# decoder.net
KiCad netlist of a schematic drawn in EAGLE
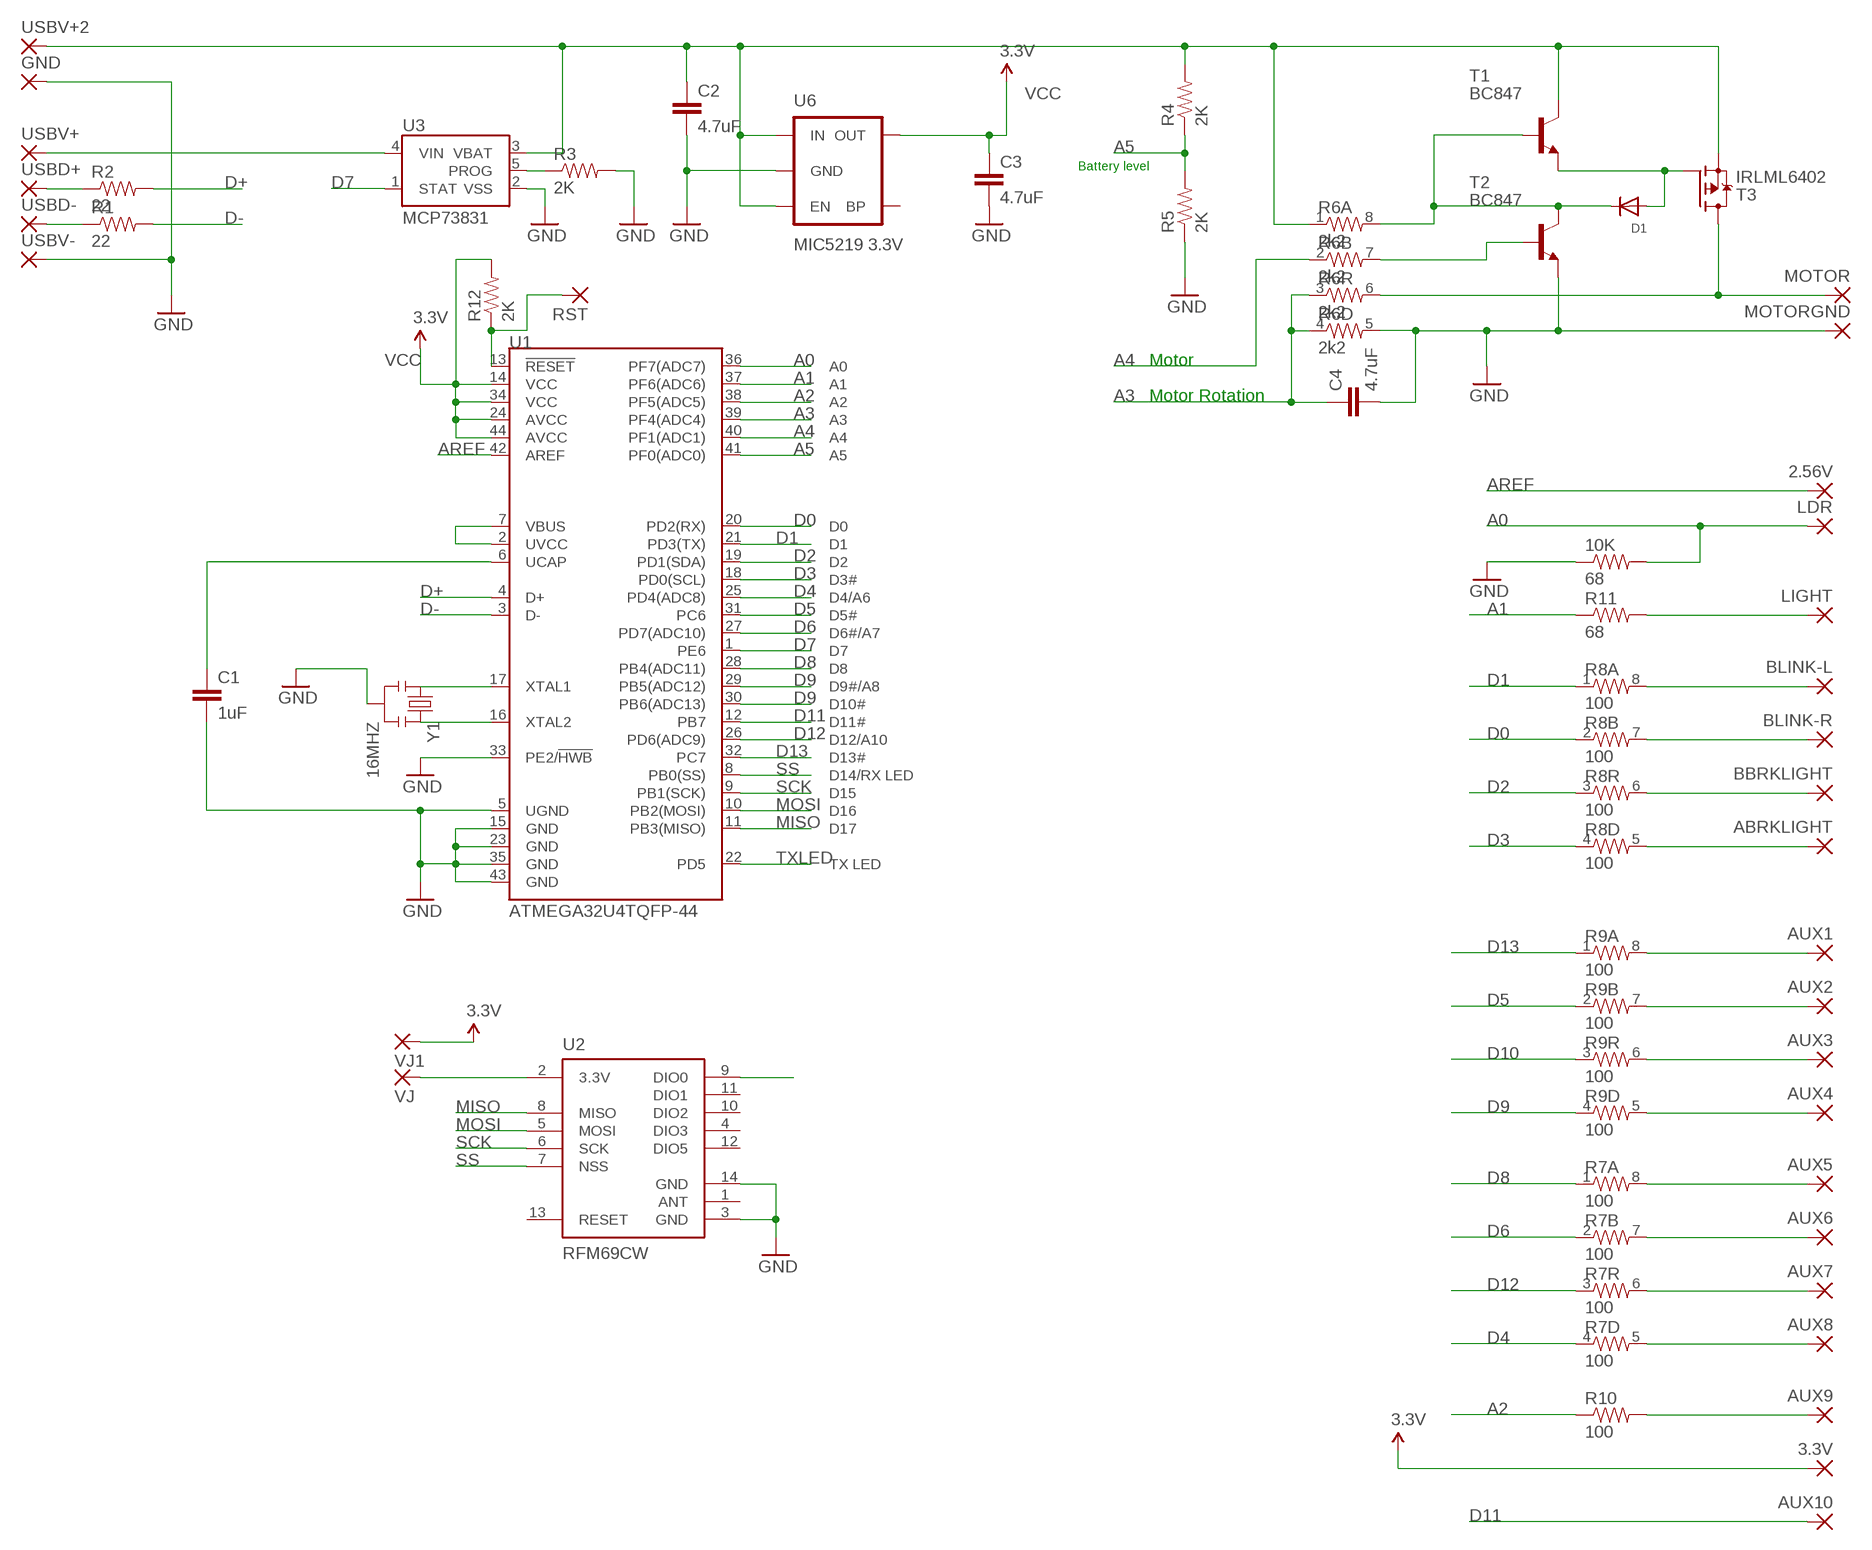
[diagram p0: schematic, sheet 1]

(export (version "E")
  (design (tool "Eeschema 10.0.6"))
  (components
    (comp (ref "2.56V")
      (value "SMD2")
      (footprint "eagle-import:SMD1,27-2,54")
      (libsource (lib "eagle-import") (part "SMD2"))
    )
    (comp (ref "3.3V")
      (value "SMD2")
      (footprint "eagle-import:SMD1,27-2,54")
      (libsource (lib "eagle-import") (part "SMD2"))
    )
    (comp (ref "10K")
      (value "68")
      (footprint "eagle-import:0603-RES")
      (libsource (lib "eagle-import") (part "RESISTOR0603-RES"))
    )
    (comp (ref "ABRKLIGHT")
      (value "SMD2")
      (footprint "eagle-import:SMD1,27-2,54")
      (libsource (lib "eagle-import") (part "SMD2"))
    )
    (comp (ref "AUX1")
      (value "SMD2")
      (footprint "eagle-import:SMD1,27-2,54")
      (libsource (lib "eagle-import") (part "SMD2"))
    )
    (comp (ref "AUX2")
      (value "SMD2")
      (footprint "eagle-import:SMD1,27-2,54")
      (libsource (lib "eagle-import") (part "SMD2"))
    )
    (comp (ref "AUX3")
      (value "SMD2")
      (footprint "eagle-import:SMD1,27-2,54")
      (libsource (lib "eagle-import") (part "SMD2"))
    )
    (comp (ref "AUX4")
      (value "SMD2")
      (footprint "eagle-import:SMD1,27-2,54")
      (libsource (lib "eagle-import") (part "SMD2"))
    )
    (comp (ref "AUX5")
      (value "SMD2")
      (footprint "eagle-import:SMD1,27-2,54")
      (libsource (lib "eagle-import") (part "SMD2"))
    )
    (comp (ref "AUX6")
      (value "SMD2")
      (footprint "eagle-import:SMD1,27-2,54")
      (libsource (lib "eagle-import") (part "SMD2"))
    )
    (comp (ref "AUX7")
      (value "SMD2")
      (footprint "eagle-import:SMD1,27-2,54")
      (libsource (lib "eagle-import") (part "SMD2"))
    )
    (comp (ref "AUX8")
      (value "SMD2")
      (footprint "eagle-import:SMD1,27-2,54")
      (libsource (lib "eagle-import") (part "SMD2"))
    )
    (comp (ref "AUX9")
      (value "SMD2")
      (footprint "eagle-import:SMD1,27-2,54")
      (libsource (lib "eagle-import") (part "SMD2"))
    )
    (comp (ref "AUX10")
      (value "SMD2")
      (footprint "eagle-import:SMD1,27-2,54")
      (libsource (lib "eagle-import") (part "SMD2"))
    )
    (comp (ref "BBRKLIGHT")
      (value "SMD2")
      (footprint "eagle-import:SMD1,27-2,54")
      (libsource (lib "eagle-import") (part "SMD2"))
    )
    (comp (ref "BLINK-L")
      (value "SMD2")
      (footprint "eagle-import:SMD1,27-2,54")
      (libsource (lib "eagle-import") (part "SMD2"))
    )
    (comp (ref "BLINK-R")
      (value "SMD2")
      (footprint "eagle-import:SMD1,27-2,54")
      (libsource (lib "eagle-import") (part "SMD2"))
    )
    (comp (ref "C1")
      (value "1uF")
      (footprint "eagle-import:0805")
      (libsource (lib "eagle-import") (part "CAP0805"))
    )
    (comp (ref "C2")
      (value "4.7uF")
      (footprint "eagle-import:0805")
      (libsource (lib "eagle-import") (part "CAP0805"))
    )
    (comp (ref "C3")
      (value "4.7uF")
      (footprint "eagle-import:0805")
      (libsource (lib "eagle-import") (part "CAP0805"))
    )
    (comp (ref "C4")
      (value "4.7uF")
      (footprint "eagle-import:0805")
      (libsource (lib "eagle-import") (part "CAP0805"))
    )
    (comp (ref "D1")
      (value "DIODESOD-523")
      (footprint "eagle-import:SOD-523")
      (libsource (lib "eagle-import") (part "DIODESOD-523"))
    )
    (comp (ref "GND")
      (value "SMD2")
      (footprint "eagle-import:SMD1,27-2,54")
      (libsource (lib "eagle-import") (part "SMD2"))
    )
    (comp (ref "LDR")
      (value "SMD2")
      (footprint "eagle-import:SMD1,27-2,54")
      (libsource (lib "eagle-import") (part "SMD2"))
    )
    (comp (ref "LIGHT")
      (value "SMD2")
      (footprint "eagle-import:SMD1,27-2,54")
      (libsource (lib "eagle-import") (part "SMD2"))
    )
    (comp (ref "MOTOR")
      (value "SMD2")
      (footprint "eagle-import:SMD1,27-2,54")
      (libsource (lib "eagle-import") (part "SMD2"))
    )
    (comp (ref "MOTORGND")
      (value "SMD2")
      (footprint "eagle-import:SMD1,27-2,54")
      (libsource (lib "eagle-import") (part "SMD2"))
    )
    (comp (ref "R1")
      (value "22")
      (footprint "eagle-import:0603-RES")
      (libsource (lib "eagle-import") (part "RESISTOR0603-RES"))
    )
    (comp (ref "R2")
      (value "22")
      (footprint "eagle-import:0603-RES")
      (libsource (lib "eagle-import") (part "RESISTOR0603-RES"))
    )
    (comp (ref "R3")
      (value "2K")
      (footprint "eagle-import:0603-RES")
      (libsource (lib "eagle-import") (part "RESISTOR0603-RES"))
    )
    (comp (ref "R4")
      (value "2K")
      (footprint "eagle-import:0603-RES")
      (libsource (lib "eagle-import") (part "RESISTOR0603-RES"))
    )
    (comp (ref "R5")
      (value "2K")
      (footprint "eagle-import:0603-RES")
      (libsource (lib "eagle-import") (part "RESISTOR0603-RES"))
    )
    (comp (ref "R6")
      (value "2k2")
      (footprint "eagle-import:0603-ARV")
      (libsource (lib "eagle-import") (part "RESISTOR-ARRAY0603-ARV"))
    )
    (comp (ref "R7")
      (value "100")
      (footprint "eagle-import:0603-ARV")
      (libsource (lib "eagle-import") (part "RESISTOR-ARRAY0603-ARV"))
    )
    (comp (ref "R8")
      (value "100")
      (footprint "eagle-import:0603-ARV")
      (libsource (lib "eagle-import") (part "RESISTOR-ARRAY0603-ARV"))
    )
    (comp (ref "R9")
      (value "100")
      (footprint "eagle-import:0603-ARV")
      (libsource (lib "eagle-import") (part "RESISTOR-ARRAY0603-ARV"))
    )
    (comp (ref "R10")
      (value "100")
      (footprint "eagle-import:0603-RES")
      (libsource (lib "eagle-import") (part "RESISTOR0603-RES"))
    )
    (comp (ref "R11")
      (value "68")
      (footprint "eagle-import:0603-RES")
      (libsource (lib "eagle-import") (part "RESISTOR0603-RES"))
    )
    (comp (ref "R12")
      (value "2K")
      (footprint "eagle-import:0603-RES")
      (libsource (lib "eagle-import") (part "RESISTOR0603-RES"))
    )
    (comp (ref "RST")
      (value "SMD2")
      (footprint "eagle-import:SMD1,27-2,54")
      (libsource (lib "eagle-import") (part "SMD2"))
    )
    (comp (ref "T1")
      (value "BC847")
      (footprint "eagle-import:SOT23")
      (libsource (lib "eagle-import") (part "BC847"))
    )
    (comp (ref "T2")
      (value "BC847")
      (footprint "eagle-import:SOT23")
      (libsource (lib "eagle-import") (part "BC847"))
    )
    (comp (ref "T3")
      (value "IRLML6402")
      (footprint "eagle-import:SOT23")
      (libsource (lib "eagle-import") (part "MOSFET-P-SOT23"))
    )
    (comp (ref "U1")
      (value "ATMEGA32U4TQFP-44")
      (footprint "eagle-import:TQFP44")
      (libsource (lib "eagle-import") (part "ATMEGA32U4TQFP-44"))
    )
    (comp (ref "U2")
      (value "RFM69CW")
      (footprint "eagle-import:RFM69CW-XXXS2")
      (libsource (lib "eagle-import") (part "RFM69CW"))
    )
    (comp (ref "U3")
      (value "MCP73831")
      (footprint "eagle-import:SOT23-5")
      (libsource (lib "eagle-import") (part "MCP73831"))
    )
    (comp (ref "U6")
      (value "MIC5219 3.3V")
      (footprint "eagle-import:SOT23-5")
      (libsource (lib "eagle-import") (part "V_REG_MIC52193.3V"))
    )
    (comp (ref "USBD+")
      (value "SMD2")
      (footprint "eagle-import:SMD1,27-2,54")
      (libsource (lib "eagle-import") (part "SMD2"))
    )
    (comp (ref "USBD-")
      (value "SMD2")
      (footprint "eagle-import:SMD1,27-2,54")
      (libsource (lib "eagle-import") (part "SMD2"))
    )
    (comp (ref "USBV+")
      (value "SMD2")
      (footprint "eagle-import:SMD1,27-2,54")
      (libsource (lib "eagle-import") (part "SMD2"))
    )
    (comp (ref "USBV+2")
      (value "SMD2")
      (footprint "eagle-import:SMD1,27-2,54")
      (libsource (lib "eagle-import") (part "SMD2"))
    )
    (comp (ref "USBV-")
      (value "SMD2")
      (footprint "eagle-import:SMD1,27-2,54")
      (libsource (lib "eagle-import") (part "SMD2"))
    )
    (comp (ref "VJ")
      (value "SMD2")
      (footprint "eagle-import:SMD1,27-2,54")
      (libsource (lib "eagle-import") (part "SMD2"))
    )
    (comp (ref "VJ1")
      (value "SMD2")
      (footprint "eagle-import:SMD1,27-2,54")
      (libsource (lib "eagle-import") (part "SMD2"))
    )
    (comp (ref "Y1")
      (value "16MHZ")
      (footprint "eagle-import:RESONATOR-SMD")
      (libsource (lib "eagle-import") (part "RESONATOR16MHZ"))
    )
  )
  (nets
    (net (code "1") (name "/A0") (class "Default")
      (node (ref "10K") (pin "2") (pinfunction "2_2") (pintype "passive"))
      (node (ref "LDR") (pin "1") (pinfunction "P_1") (pintype "passive"))
      (node (ref "U1") (pin "36") (pinfunction "PF7(ADC7)_36") (pintype "bidirectional"))
    )
    (net (code "2") (name "/A1") (class "Default")
      (node (ref "R11") (pin "1") (pinfunction "1_1") (pintype "passive"))
      (node (ref "U1") (pin "37") (pinfunction "PF6(ADC6)_37") (pintype "bidirectional"))
    )
    (net (code "3") (name "/A2") (class "Default")
      (node (ref "R10") (pin "1") (pinfunction "1_1") (pintype "passive"))
      (node (ref "U1") (pin "38") (pinfunction "PF5(ADC5)_38") (pintype "bidirectional"))
    )
    (net (code "4") (name "/A3") (class "Default")
      (node (ref "C4") (pin "1") (pinfunction "1_1") (pintype "passive"))
      (node (ref "R6") (pin "3") (pinfunction "1_3") (pintype "passive"))
      (node (ref "R6") (pin "4") (pinfunction "1_4") (pintype "passive"))
      (node (ref "U1") (pin "39") (pinfunction "PF4(ADC4)_39") (pintype "bidirectional"))
    )
    (net (code "5") (name "/A4") (class "Default")
      (node (ref "R6") (pin "2") (pinfunction "1_2") (pintype "passive"))
      (node (ref "U1") (pin "40") (pinfunction "PF1(ADC1)_40") (pintype "bidirectional"))
    )
    (net (code "6") (name "/A5") (class "Default")
      (node (ref "R4") (pin "1") (pinfunction "1_1") (pintype "passive"))
      (node (ref "R5") (pin "2") (pinfunction "2_2") (pintype "passive"))
      (node (ref "U1") (pin "41") (pinfunction "PF0(ADC0)_41") (pintype "bidirectional"))
    )
    (net (code "7") (name "/AREF") (class "Default")
      (node (ref "2.56V") (pin "1") (pinfunction "P_1") (pintype "passive"))
      (node (ref "U1") (pin "42") (pinfunction "AREF_42") (pintype "bidirectional"))
    )
    (net (code "8") (name "/D+") (class "Default")
      (node (ref "R2") (pin "2") (pinfunction "2_2") (pintype "passive"))
      (node (ref "U1") (pin "4") (pinfunction "D+_4") (pintype "bidirectional"))
    )
    (net (code "9") (name "/D-") (class "Default")
      (node (ref "R1") (pin "2") (pinfunction "2_2") (pintype "passive"))
      (node (ref "U1") (pin "3") (pinfunction "D-_3") (pintype "bidirectional"))
    )
    (net (code "10") (name "/D0") (class "Default")
      (node (ref "R8") (pin "2") (pinfunction "1_2") (pintype "passive"))
      (node (ref "U1") (pin "20") (pinfunction "PD2(RX)_20") (pintype "bidirectional"))
    )
    (net (code "11") (name "/D1") (class "Default")
      (node (ref "R8") (pin "1") (pinfunction "1_1") (pintype "passive"))
      (node (ref "U1") (pin "21") (pinfunction "PD3(TX)_21") (pintype "bidirectional"))
    )
    (net (code "12") (name "/D2") (class "Default")
      (node (ref "R8") (pin "3") (pinfunction "1_3") (pintype "passive"))
      (node (ref "U1") (pin "19") (pinfunction "PD1(SDA)_19") (pintype "bidirectional"))
      (node (ref "U2") (pin "9") (pinfunction "DIO0_9") (pintype "bidirectional"))
    )
    (net (code "13") (name "/D3") (class "Default")
      (node (ref "R8") (pin "4") (pinfunction "1_4") (pintype "passive"))
      (node (ref "U1") (pin "18") (pinfunction "PD0(SCL)_18") (pintype "bidirectional"))
    )
    (net (code "14") (name "/D4") (class "Default")
      (node (ref "R7") (pin "4") (pinfunction "1_4") (pintype "passive"))
      (node (ref "U1") (pin "25") (pinfunction "PD4(ADC8)_25") (pintype "bidirectional"))
    )
    (net (code "15") (name "/D5") (class "Default")
      (node (ref "R9") (pin "2") (pinfunction "1_2") (pintype "passive"))
      (node (ref "U1") (pin "31") (pinfunction "PC6_31") (pintype "bidirectional"))
    )
    (net (code "16") (name "/D6") (class "Default")
      (node (ref "R7") (pin "2") (pinfunction "1_2") (pintype "passive"))
      (node (ref "U1") (pin "27") (pinfunction "PD7(ADC10)_27") (pintype "bidirectional"))
    )
    (net (code "17") (name "/D7") (class "Default")
      (node (ref "U1") (pin "1") (pinfunction "PE6_1") (pintype "bidirectional"))
      (node (ref "U3") (pin "1") (pinfunction "STAT_1") (pintype "output"))
    )
    (net (code "18") (name "/D8") (class "Default")
      (node (ref "R7") (pin "1") (pinfunction "1_1") (pintype "passive"))
      (node (ref "U1") (pin "28") (pinfunction "PB4(ADC11)_28") (pintype "bidirectional"))
    )
    (net (code "19") (name "/D9") (class "Default")
      (node (ref "R9") (pin "4") (pinfunction "1_4") (pintype "passive"))
      (node (ref "U1") (pin "29") (pinfunction "PB5(ADC12)_29") (pintype "bidirectional"))
    )
    (net (code "20") (name "/D10") (class "Default")
      (node (ref "R9") (pin "3") (pinfunction "1_3") (pintype "passive"))
      (node (ref "U1") (pin "30") (pinfunction "PB6(ADC13)_30") (pintype "bidirectional"))
    )
    (net (code "21") (name "/D11") (class "Default")
      (node (ref "AUX10") (pin "1") (pinfunction "P_1") (pintype "passive"))
      (node (ref "U1") (pin "12") (pinfunction "PB7_12") (pintype "bidirectional"))
    )
    (net (code "22") (name "/D12") (class "Default")
      (node (ref "R7") (pin "3") (pinfunction "1_3") (pintype "passive"))
      (node (ref "U1") (pin "26") (pinfunction "PD6(ADC9)_26") (pintype "bidirectional"))
    )
    (net (code "23") (name "/D13") (class "Default")
      (node (ref "R9") (pin "1") (pinfunction "1_1") (pintype "passive"))
      (node (ref "U1") (pin "32") (pinfunction "PC7_32") (pintype "bidirectional"))
    )
    (net (code "24") (name "/MISO") (class "Default")
      (node (ref "U1") (pin "11") (pinfunction "PB3(MISO)_11") (pintype "bidirectional"))
      (node (ref "U2") (pin "8") (pinfunction "MISO_8") (pintype "bidirectional"))
    )
    (net (code "25") (name "/MOSI") (class "Default")
      (node (ref "U1") (pin "10") (pinfunction "PB2(MOSI)_10") (pintype "bidirectional"))
      (node (ref "U2") (pin "5") (pinfunction "MOSI_5") (pintype "input"))
    )
    (net (code "26") (name "/SCK") (class "Default")
      (node (ref "U1") (pin "9") (pinfunction "PB1(SCK)_9") (pintype "bidirectional"))
      (node (ref "U2") (pin "6") (pinfunction "SCK_6") (pintype "input"))
    )
    (net (code "27") (name "/SS") (class "Default")
      (node (ref "U1") (pin "8") (pinfunction "PB0(SS)_8") (pintype "bidirectional"))
      (node (ref "U2") (pin "7") (pinfunction "NSS_7") (pintype "input"))
    )
    (net (code "28") (name "/TXLED") (class "Default")
      (node (ref "U1") (pin "22") (pinfunction "PD5_22") (pintype "bidirectional"))
    )
    (net (code "29") (name "3.3V") (class "Default")
      (node (ref "3.3V") (pin "1") (pinfunction "P_1") (pintype "passive"))
      (node (ref "C3") (pin "1") (pinfunction "1_1") (pintype "passive"))
      (node (ref "R12") (pin "2") (pinfunction "2_2") (pintype "passive"))
      (node (ref "U1") (pin "14") (pinfunction "VCC_14") (pintype "bidirectional"))
      (node (ref "U1") (pin "24") (pinfunction "AVCC_24") (pintype "bidirectional"))
      (node (ref "U1") (pin "34") (pinfunction "VCC_34") (pintype "bidirectional"))
      (node (ref "U1") (pin "44") (pinfunction "AVCC_44") (pintype "bidirectional"))
      (node (ref "U6") (pin "5") (pinfunction "OUT_5") (pintype "passive"))
      (node (ref "VJ1") (pin "1") (pinfunction "P_1") (pintype "passive"))
    )
    (net (code "30") (name "GND") (class "Default")
      (node (ref "10K") (pin "1") (pinfunction "1_1") (pintype "passive"))
      (node (ref "C1") (pin "2") (pinfunction "2_2") (pintype "passive"))
      (node (ref "C2") (pin "2") (pinfunction "2_2") (pintype "passive"))
      (node (ref "C3") (pin "2") (pinfunction "2_2") (pintype "passive"))
      (node (ref "C4") (pin "2") (pinfunction "2_2") (pintype "passive"))
      (node (ref "GND") (pin "1") (pinfunction "P_1") (pintype "passive"))
      (node (ref "MOTORGND") (pin "1") (pinfunction "P_1") (pintype "passive"))
      (node (ref "R3") (pin "2") (pinfunction "2_2") (pintype "passive"))
      (node (ref "R5") (pin "1") (pinfunction "1_1") (pintype "passive"))
      (node (ref "R6") (pin "5") (pinfunction "2_5") (pintype "passive"))
      (node (ref "T2") (pin "2") (pinfunction "E_2") (pintype "passive"))
      (node (ref "U1") (pin "15") (pinfunction "GND_15") (pintype "bidirectional"))
      (node (ref "U1") (pin "23") (pinfunction "GND_23") (pintype "bidirectional"))
      (node (ref "U1") (pin "33") (pinfunction "PE2/~{HWB}_33") (pintype "bidirectional"))
      (node (ref "U1") (pin "35") (pinfunction "GND_35") (pintype "bidirectional"))
      (node (ref "U1") (pin "43") (pinfunction "GND_43") (pintype "bidirectional"))
      (node (ref "U1") (pin "5") (pinfunction "UGND_5") (pintype "bidirectional"))
      (node (ref "U2") (pin "14") (pinfunction "GND_14") (pintype "power_in"))
      (node (ref "U2") (pin "3") (pinfunction "GND_3") (pintype "power_in"))
      (node (ref "U3") (pin "2") (pinfunction "VSS_2") (pintype "power_in"))
      (node (ref "U6") (pin "2") (pinfunction "GND_2") (pintype "input"))
      (node (ref "USBV-") (pin "1") (pinfunction "P_1") (pintype "passive"))
      (node (ref "Y1") (pin "2") (pinfunction "2_2") (pintype "passive"))
    )
    (net (code "31") (name "Net-(ABRKLIGHT-P)") (class "Default")
      (node (ref "ABRKLIGHT") (pin "1") (pinfunction "P_1") (pintype "passive"))
      (node (ref "R8") (pin "5") (pinfunction "2_5") (pintype "passive"))
    )
    (net (code "32") (name "Net-(AUX1-P)") (class "Default")
      (node (ref "AUX1") (pin "1") (pinfunction "P_1") (pintype "passive"))
      (node (ref "R9") (pin "8") (pinfunction "2_8") (pintype "passive"))
    )
    (net (code "33") (name "Net-(AUX2-P)") (class "Default")
      (node (ref "AUX2") (pin "1") (pinfunction "P_1") (pintype "passive"))
      (node (ref "R9") (pin "7") (pinfunction "2_7") (pintype "passive"))
    )
    (net (code "34") (name "Net-(AUX3-P)") (class "Default")
      (node (ref "AUX3") (pin "1") (pinfunction "P_1") (pintype "passive"))
      (node (ref "R9") (pin "6") (pinfunction "2_6") (pintype "passive"))
    )
    (net (code "35") (name "Net-(AUX4-P)") (class "Default")
      (node (ref "AUX4") (pin "1") (pinfunction "P_1") (pintype "passive"))
      (node (ref "R9") (pin "5") (pinfunction "2_5") (pintype "passive"))
    )
    (net (code "36") (name "Net-(AUX5-P)") (class "Default")
      (node (ref "AUX5") (pin "1") (pinfunction "P_1") (pintype "passive"))
      (node (ref "R7") (pin "8") (pinfunction "2_8") (pintype "passive"))
    )
    (net (code "37") (name "Net-(AUX6-P)") (class "Default")
      (node (ref "AUX6") (pin "1") (pinfunction "P_1") (pintype "passive"))
      (node (ref "R7") (pin "7") (pinfunction "2_7") (pintype "passive"))
    )
    (net (code "38") (name "Net-(AUX7-P)") (class "Default")
      (node (ref "AUX7") (pin "1") (pinfunction "P_1") (pintype "passive"))
      (node (ref "R7") (pin "6") (pinfunction "2_6") (pintype "passive"))
    )
    (net (code "39") (name "Net-(AUX8-P)") (class "Default")
      (node (ref "AUX8") (pin "1") (pinfunction "P_1") (pintype "passive"))
      (node (ref "R7") (pin "5") (pinfunction "2_5") (pintype "passive"))
    )
    (net (code "40") (name "Net-(AUX9-P)") (class "Default")
      (node (ref "AUX9") (pin "1") (pinfunction "P_1") (pintype "passive"))
      (node (ref "R10") (pin "2") (pinfunction "2_2") (pintype "passive"))
    )
    (net (code "41") (name "Net-(BBRKLIGHT-P)") (class "Default")
      (node (ref "BBRKLIGHT") (pin "1") (pinfunction "P_1") (pintype "passive"))
      (node (ref "R8") (pin "6") (pinfunction "2_6") (pintype "passive"))
    )
    (net (code "42") (name "Net-(BLINK-L-P)") (class "Default")
      (node (ref "BLINK-L") (pin "1") (pinfunction "P_1") (pintype "passive"))
      (node (ref "R8") (pin "8") (pinfunction "2_8") (pintype "passive"))
    )
    (net (code "43") (name "Net-(BLINK-R-P)") (class "Default")
      (node (ref "BLINK-R") (pin "1") (pinfunction "P_1") (pintype "passive"))
      (node (ref "R8") (pin "7") (pinfunction "2_7") (pintype "passive"))
    )
    (net (code "44") (name "Net-(D1-C)") (class "Default")
      (node (ref "D1") (pin "K") (pinfunction "C_K") (pintype "passive"))
      (node (ref "R6") (pin "8") (pinfunction "2_8") (pintype "passive"))
      (node (ref "T1") (pin "1") (pinfunction "B_1") (pintype "passive"))
      (node (ref "T2") (pin "3") (pinfunction "C_3") (pintype "passive"))
    )
    (net (code "45") (name "Net-(LIGHT-P)") (class "Default")
      (node (ref "LIGHT") (pin "1") (pinfunction "P_1") (pintype "passive"))
      (node (ref "R11") (pin "2") (pinfunction "2_2") (pintype "passive"))
    )
    (net (code "46") (name "Net-(MOTOR-P)") (class "Default")
      (node (ref "MOTOR") (pin "1") (pinfunction "P_1") (pintype "passive"))
      (node (ref "R6") (pin "6") (pinfunction "2_6") (pintype "passive"))
      (node (ref "T3") (pin "3") (pinfunction "D_3") (pintype "passive"))
    )
    (net (code "47") (name "Net-(R6B-2)") (class "Default")
      (node (ref "R6") (pin "7") (pinfunction "2_7") (pintype "passive"))
      (node (ref "T2") (pin "1") (pinfunction "B_1") (pintype "passive"))
    )
    (net (code "48") (name "Net-(RST-P)") (class "Default")
      (node (ref "R12") (pin "1") (pinfunction "1_1") (pintype "passive"))
      (node (ref "RST") (pin "1") (pinfunction "P_1") (pintype "passive"))
      (node (ref "U1") (pin "13") (pinfunction "~{RESET}_13") (pintype "bidirectional"))
    )
    (net (code "49") (name "Net-(T1-C)") (class "Default")
      (node (ref "C2") (pin "1") (pinfunction "1_1") (pintype "passive"))
      (node (ref "R4") (pin "2") (pinfunction "2_2") (pintype "passive"))
      (node (ref "R6") (pin "1") (pinfunction "1_1") (pintype "passive"))
      (node (ref "T1") (pin "3") (pinfunction "C_3") (pintype "passive"))
      (node (ref "T3") (pin "2") (pinfunction "S_2") (pintype "passive"))
      (node (ref "U3") (pin "3") (pinfunction "VBAT_3") (pintype "power_in"))
      (node (ref "U6") (pin "1") (pinfunction "IN_1") (pintype "input"))
      (node (ref "U6") (pin "3") (pinfunction "EN_3") (pintype "input"))
      (node (ref "USBV+2") (pin "1") (pinfunction "P_1") (pintype "passive"))
    )
    (net (code "50") (name "Net-(T1-E)") (class "Default")
      (node (ref "D1") (pin "A") (pinfunction "A_A") (pintype "passive"))
      (node (ref "T1") (pin "2") (pinfunction "E_2") (pintype "passive"))
      (node (ref "T3") (pin "1") (pinfunction "G_1") (pintype "passive"))
    )
    (net (code "51") (name "Net-(U1-UCAP)") (class "Default")
      (node (ref "C1") (pin "1") (pinfunction "1_1") (pintype "passive"))
      (node (ref "U1") (pin "6") (pinfunction "UCAP_6") (pintype "bidirectional"))
    )
    (net (code "52") (name "Net-(U1-UVCC)") (class "Default")
      (node (ref "U1") (pin "2") (pinfunction "UVCC_2") (pintype "bidirectional"))
      (node (ref "U1") (pin "7") (pinfunction "VBUS_7") (pintype "bidirectional"))
    )
    (net (code "53") (name "Net-(U1-XTAL1)") (class "Default")
      (node (ref "U1") (pin "17") (pinfunction "XTAL1_17") (pintype "bidirectional"))
      (node (ref "Y1") (pin "1") (pinfunction "1_1") (pintype "passive"))
    )
    (net (code "54") (name "Net-(U1-XTAL2)") (class "Default")
      (node (ref "U1") (pin "16") (pinfunction "XTAL2_16") (pintype "bidirectional"))
      (node (ref "Y1") (pin "3") (pinfunction "3_3") (pintype "passive"))
    )
    (net (code "55") (name "Net-(U2-3.3V)") (class "Default")
      (node (ref "U2") (pin "2") (pinfunction "3.3V_2") (pintype "power_in"))
      (node (ref "VJ") (pin "1") (pinfunction "P_1") (pintype "passive"))
    )
    (net (code "56") (name "Net-(U3-PROG)") (class "Default")
      (node (ref "R3") (pin "1") (pinfunction "1_1") (pintype "passive"))
      (node (ref "U3") (pin "5") (pinfunction "PROG_5") (pintype "input"))
    )
    (net (code "57") (name "Net-(U3-VIN)") (class "Default")
      (node (ref "U3") (pin "4") (pinfunction "VIN_4") (pintype "power_in"))
      (node (ref "USBV+") (pin "1") (pinfunction "P_1") (pintype "passive"))
    )
    (net (code "58") (name "Net-(USBD+-P)") (class "Default")
      (node (ref "R2") (pin "1") (pinfunction "1_1") (pintype "passive"))
      (node (ref "USBD+") (pin "1") (pinfunction "P_1") (pintype "passive"))
    )
    (net (code "59") (name "Net-(USBD--P)") (class "Default")
      (node (ref "R1") (pin "1") (pinfunction "1_1") (pintype "passive"))
      (node (ref "USBD-") (pin "1") (pinfunction "P_1") (pintype "passive"))
    )
    (net (code "60") (name "unconnected-(U2-ANT-Pad1)") (class "Default")
      (node (ref "U2") (pin "1") (pinfunction "ANT_1") (pintype "passive"))
    )
    (net (code "61") (name "unconnected-(U2-DIO1-Pad11)") (class "Default")
      (node (ref "U2") (pin "11") (pinfunction "DIO1_11") (pintype "bidirectional"))
    )
    (net (code "62") (name "unconnected-(U2-DIO2-Pad10)") (class "Default")
      (node (ref "U2") (pin "10") (pinfunction "DIO2_10") (pintype "bidirectional"))
    )
    (net (code "63") (name "unconnected-(U2-DIO3-Pad4)") (class "Default")
      (node (ref "U2") (pin "4") (pinfunction "DIO3_4") (pintype "bidirectional"))
    )
    (net (code "64") (name "unconnected-(U2-DIO5-Pad12)") (class "Default")
      (node (ref "U2") (pin "12") (pinfunction "DIO5_12") (pintype "bidirectional"))
    )
    (net (code "65") (name "unconnected-(U2-RESET-Pad13)") (class "Default")
      (node (ref "U2") (pin "13") (pinfunction "RESET_13") (pintype "input"))
    )
    (net (code "66") (name "unconnected-(U6-BP-Pad4)") (class "Default")
      (node (ref "U6") (pin "4") (pinfunction "BP_4") (pintype "input"))
    )
  )
)
